# LightSensors_SCH.net
KiCad netlist of a schematic drawn in Altium Designer
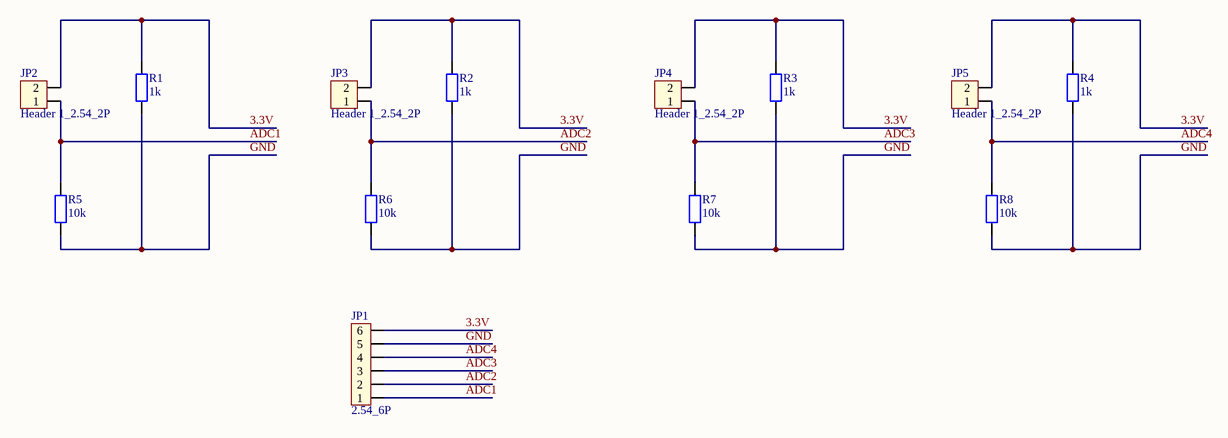
[diagram p0: LightSensors_SCH.SchDoc]

(export (version "E")
  (design (tool "Eeschema 10.0.6"))
  (components
    (comp (ref "JP1")
      (value "2.54_6P")
      (footprint "JP6")
      (description "Cắm")
      (libsource (lib "THU VIEN SCH") (part "Jum Don Duc 2.54_6P"))
    )
    (comp (ref "JP2")
      (value "Header 1_2.54_2P")
      (footprint "Header_Duc Cong_2P 2.54")
      (description "Cắm")
      (libsource (lib "THU VIEN SCH") (part "Header 1_2.54_2P"))
    )
    (comp (ref "JP3")
      (value "Header 1_2.54_2P")
      (footprint "Header_Duc Cong_2P 2.54")
      (description "Cắm")
      (libsource (lib "THU VIEN SCH") (part "Header 1_2.54_2P"))
    )
    (comp (ref "JP4")
      (value "Header 1_2.54_2P")
      (footprint "Header_Duc Cong_2P 2.54")
      (description "Cắm")
      (libsource (lib "THU VIEN SCH") (part "Header 1_2.54_2P"))
    )
    (comp (ref "JP5")
      (value "Header 1_2.54_2P")
      (footprint "Header_Duc Cong_2P 2.54")
      (description "Cắm")
      (libsource (lib "THU VIEN SCH") (part "Header 1_2.54_2P"))
    )
    (comp (ref "R1")
      (value "1k")
      (footprint "tro vach 1/4w")
      (description "Cắm")
      (libsource (lib "THU VIEN SCH") (part "Tro Vach 1/4W 5% 1k"))
    )
    (comp (ref "R2")
      (value "1k")
      (footprint "tro vach 1/4w")
      (description "Cắm")
      (libsource (lib "THU VIEN SCH") (part "Tro Vach 1/4W 5% 1k"))
    )
    (comp (ref "R3")
      (value "1k")
      (footprint "tro vach 1/4w")
      (description "Cắm")
      (libsource (lib "THU VIEN SCH") (part "Tro Vach 1/4W 5% 1k"))
    )
    (comp (ref "R4")
      (value "1k")
      (footprint "tro vach 1/4w")
      (description "Cắm")
      (libsource (lib "THU VIEN SCH") (part "Tro Vach 1/4W 5% 1k"))
    )
    (comp (ref "R5")
      (value "10k")
      (footprint "tro vach 1/4w")
      (description "Căm")
      (libsource (lib "THU VIEN SCH") (part "Tro Vach 1/4W 5% 10k"))
    )
    (comp (ref "R6")
      (value "10k")
      (footprint "tro vach 1/4w")
      (description "Căm")
      (libsource (lib "THU VIEN SCH") (part "Tro Vach 1/4W 5% 10k"))
    )
    (comp (ref "R7")
      (value "10k")
      (footprint "tro vach 1/4w")
      (description "Căm")
      (libsource (lib "THU VIEN SCH") (part "Tro Vach 1/4W 5% 10k"))
    )
    (comp (ref "R8")
      (value "10k")
      (footprint "tro vach 1/4w")
      (description "Căm")
      (libsource (lib "THU VIEN SCH") (part "Tro Vach 1/4W 5% 10k"))
    )
  )
  (nets
    (net (code "1") (name "/3.3V") (class "Default")
      (node (ref "JP1") (pin "6") (pinfunction "6_6") (pintype "passive"))
      (node (ref "JP2") (pin "2") (pinfunction "2_2") (pintype "passive"))
      (node (ref "JP3") (pin "2") (pinfunction "2_2") (pintype "passive"))
      (node (ref "JP4") (pin "2") (pinfunction "2_2") (pintype "passive"))
      (node (ref "JP5") (pin "2") (pinfunction "2_2") (pintype "passive"))
      (node (ref "R1") (pin "2") (pinfunction "2_2") (pintype "passive"))
      (node (ref "R2") (pin "2") (pinfunction "2_2") (pintype "passive"))
      (node (ref "R3") (pin "2") (pinfunction "2_2") (pintype "passive"))
      (node (ref "R4") (pin "2") (pinfunction "2_2") (pintype "passive"))
    )
    (net (code "2") (name "/ADC1") (class "Default")
      (node (ref "JP1") (pin "1") (pinfunction "1_1") (pintype "passive"))
      (node (ref "JP2") (pin "1") (pinfunction "1_1") (pintype "passive"))
      (node (ref "R5") (pin "2") (pinfunction "2_2") (pintype "passive"))
    )
    (net (code "3") (name "/ADC2") (class "Default")
      (node (ref "JP1") (pin "2") (pinfunction "2_2") (pintype "passive"))
      (node (ref "JP3") (pin "1") (pinfunction "1_1") (pintype "passive"))
      (node (ref "R6") (pin "2") (pinfunction "2_2") (pintype "passive"))
    )
    (net (code "4") (name "/ADC3") (class "Default")
      (node (ref "JP1") (pin "3") (pinfunction "3_3") (pintype "passive"))
      (node (ref "JP4") (pin "1") (pinfunction "1_1") (pintype "passive"))
      (node (ref "R7") (pin "2") (pinfunction "2_2") (pintype "passive"))
    )
    (net (code "5") (name "/ADC4") (class "Default")
      (node (ref "JP1") (pin "4") (pinfunction "4_4") (pintype "passive"))
      (node (ref "JP5") (pin "1") (pinfunction "1_1") (pintype "passive"))
      (node (ref "R8") (pin "2") (pinfunction "2_2") (pintype "passive"))
    )
    (net (code "6") (name "/GND") (class "Default")
      (node (ref "JP1") (pin "5") (pinfunction "5_5") (pintype "passive"))
      (node (ref "R1") (pin "1") (pinfunction "1_1") (pintype "passive"))
      (node (ref "R2") (pin "1") (pinfunction "1_1") (pintype "passive"))
      (node (ref "R3") (pin "1") (pinfunction "1_1") (pintype "passive"))
      (node (ref "R4") (pin "1") (pinfunction "1_1") (pintype "passive"))
      (node (ref "R5") (pin "1") (pinfunction "1_1") (pintype "passive"))
      (node (ref "R6") (pin "1") (pinfunction "1_1") (pintype "passive"))
      (node (ref "R7") (pin "1") (pinfunction "1_1") (pintype "passive"))
      (node (ref "R8") (pin "1") (pinfunction "1_1") (pintype "passive"))
    )
  )
)
